# thumper2_v0001.net
KiCad netlist of a schematic drawn in EAGLE
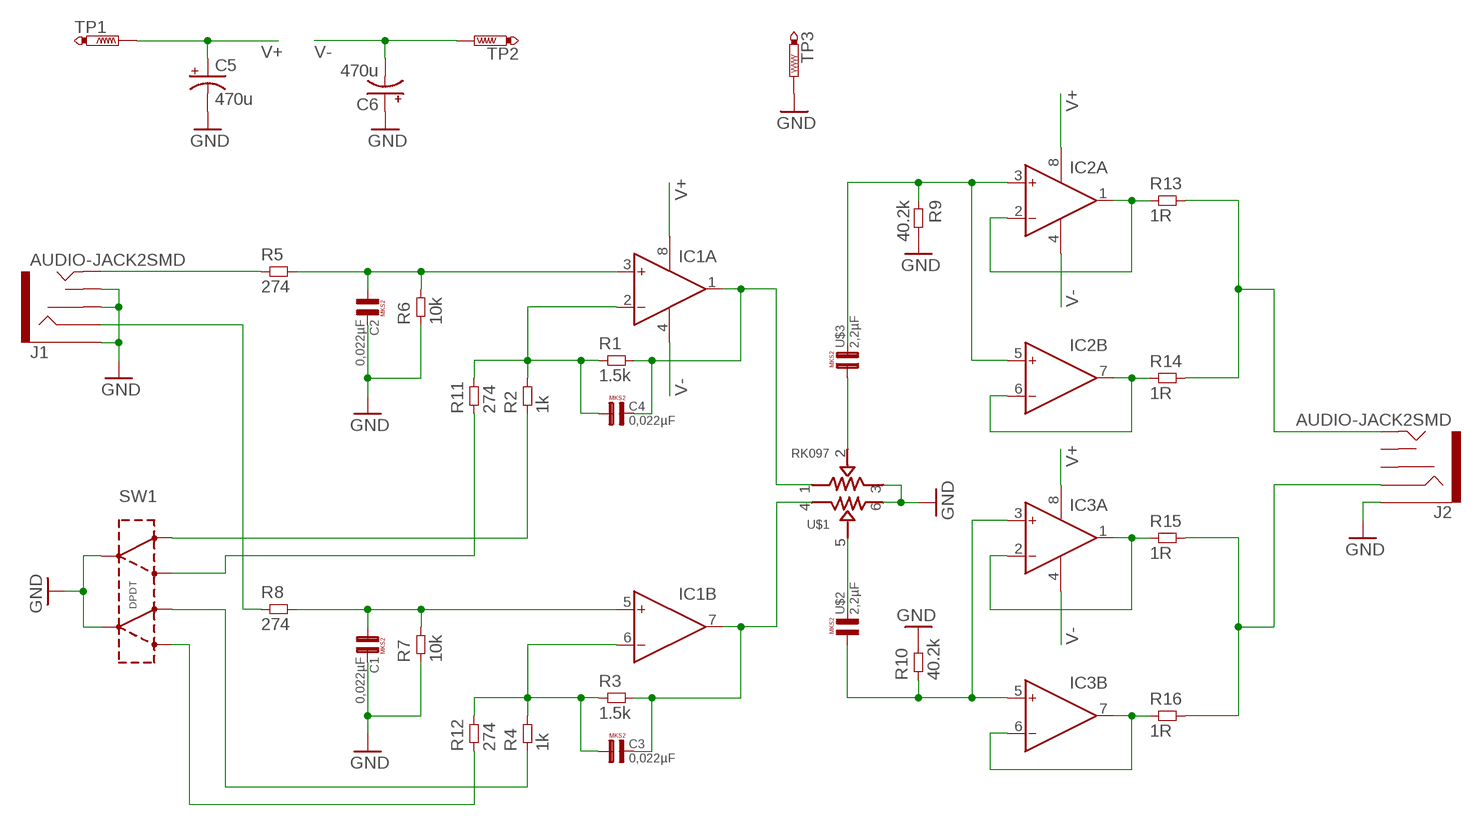
[diagram p0: schematic, sheet 1]

(export (version "E")
  (design (tool "Eeschema 10.0.6"))
  (components
    (comp (ref "C1")
      (value "0,022µF")
      (footprint "eagle-import:R5B2K5")
      (libsource (lib "eagle-import") (part "0,022µF"))
    )
    (comp (ref "C2")
      (value "0,022µF")
      (footprint "eagle-import:R5B2K5")
      (libsource (lib "eagle-import") (part "0,022µF"))
    )
    (comp (ref "C3")
      (value "0,022µF")
      (footprint "eagle-import:R5B2K5")
      (libsource (lib "eagle-import") (part "0,022µF"))
    )
    (comp (ref "C4")
      (value "0,022µF")
      (footprint "eagle-import:R5B2K5")
      (libsource (lib "eagle-import") (part "0,022µF"))
    )
    (comp (ref "C5")
      (value "470u")
      (footprint "eagle-import:153CLV-1010")
      (libsource (lib "eagle-import") (part "CPOL-US153CLV-1010"))
    )
    (comp (ref "C6")
      (value "470u")
      (footprint "eagle-import:153CLV-1010")
      (libsource (lib "eagle-import") (part "CPOL-US153CLV-1010"))
    )
    (comp (ref "IC1")
      (value "AD8620R")
      (footprint "eagle-import:SO8")
      (fields (field (name "MF") "ALTERA CORPORATION") (field (name "MPN") "AD8620ARZ"))
      (libsource (lib "eagle-import") (part "AD8620R"))
    )
    (comp (ref "IC2")
      (value "AD8620R")
      (footprint "eagle-import:SO8")
      (fields (field (name "MF") "ALTERA CORPORATION") (field (name "MPN") "AD8620ARZ"))
      (libsource (lib "eagle-import") (part "AD8620R"))
    )
    (comp (ref "IC3")
      (value "AD8620R")
      (footprint "eagle-import:SO8")
      (fields (field (name "MF") "ALTERA CORPORATION") (field (name "MPN") "AD8620ARZ"))
      (libsource (lib "eagle-import") (part "AD8620R"))
    )
    (comp (ref "J1")
      (value "AUDIO-JACK2SMD")
      (footprint "eagle-import:AUDIO-JACK-3.5MM-SMD")
      (libsource (lib "eagle-import") (part "AUDIO-JACK2SMD"))
    )
    (comp (ref "J2")
      (value "AUDIO-JACK2SMD")
      (footprint "eagle-import:AUDIO-JACK-3.5MM-SMD")
      (libsource (lib "eagle-import") (part "AUDIO-JACK2SMD"))
    )
    (comp (ref "R1")
      (value "1.5k")
      (footprint "eagle-import:0603L3")
      (libsource (lib "eagle-import") (part "RES0603L3"))
    )
    (comp (ref "R2")
      (value "1k")
      (footprint "eagle-import:0603L3")
      (libsource (lib "eagle-import") (part "RES0603L3"))
    )
    (comp (ref "R3")
      (value "1.5k")
      (footprint "eagle-import:0603L3")
      (libsource (lib "eagle-import") (part "RES0603L3"))
    )
    (comp (ref "R4")
      (value "1k")
      (footprint "eagle-import:0603L3")
      (libsource (lib "eagle-import") (part "RES0603L3"))
    )
    (comp (ref "R5")
      (value "274")
      (footprint "eagle-import:0603L3")
      (libsource (lib "eagle-import") (part "RES0603L3"))
    )
    (comp (ref "R6")
      (value "10k")
      (footprint "eagle-import:0603L3")
      (libsource (lib "eagle-import") (part "RES0603L3"))
    )
    (comp (ref "R7")
      (value "10k")
      (footprint "eagle-import:0603L3")
      (libsource (lib "eagle-import") (part "RES0603L3"))
    )
    (comp (ref "R8")
      (value "274")
      (footprint "eagle-import:0603L3")
      (libsource (lib "eagle-import") (part "RES0603L3"))
    )
    (comp (ref "R9")
      (value "40.2k")
      (footprint "eagle-import:0603L3")
      (libsource (lib "eagle-import") (part "RES0603L3"))
    )
    (comp (ref "R10")
      (value "40.2k")
      (footprint "eagle-import:0603L3")
      (libsource (lib "eagle-import") (part "RES0603L3"))
    )
    (comp (ref "R11")
      (value "274")
      (footprint "eagle-import:0603L3")
      (libsource (lib "eagle-import") (part "RES0603L3"))
    )
    (comp (ref "R12")
      (value "274")
      (footprint "eagle-import:0603L3")
      (libsource (lib "eagle-import") (part "RES0603L3"))
    )
    (comp (ref "R13")
      (value "1R")
      (footprint "eagle-import:1206L3")
      (libsource (lib "eagle-import") (part "RES1206L3"))
    )
    (comp (ref "R14")
      (value "1R")
      (footprint "eagle-import:1206L3")
      (libsource (lib "eagle-import") (part "RES1206L3"))
    )
    (comp (ref "R15")
      (value "1R")
      (footprint "eagle-import:1206L3")
      (libsource (lib "eagle-import") (part "RES1206L3"))
    )
    (comp (ref "R16")
      (value "1R")
      (footprint "eagle-import:1206L3")
      (libsource (lib "eagle-import") (part "RES1206L3"))
    )
    (comp (ref "SW1")
      (value "DPDTDPDT-2X2.5")
      (footprint "eagle-import:DPDT-2X2.5")
      (libsource (lib "eagle-import") (part "DPDTDPDT-2X2.5"))
    )
    (comp (ref "TP1")
      (value "PTR1PAD1-20")
      (footprint "eagle-import:P1-20")
      (libsource (lib "eagle-import") (part "PTR1PAD1-20"))
    )
    (comp (ref "TP2")
      (value "PTR1PAD1-20")
      (footprint "eagle-import:P1-20")
      (libsource (lib "eagle-import") (part "PTR1PAD1-20"))
    )
    (comp (ref "TP3")
      (value "PTR1PAD1-20")
      (footprint "eagle-import:P1-20")
      (libsource (lib "eagle-import") (part "PTR1PAD1-20"))
    )
    (comp (ref "U$1")
      (value "RK097")
      (footprint "eagle-import:RK097")
      (libsource (lib "eagle-import") (part "RK097"))
    )
    (comp (ref "U$2")
      (value "2,2µF")
      (footprint "eagle-import:R5B7K2")
      (libsource (lib "eagle-import") (part "2,2µF"))
    )
    (comp (ref "U$3")
      (value "2,2µF")
      (footprint "eagle-import:R5B7K2")
      (libsource (lib "eagle-import") (part "2,2µF"))
    )
  )
  (nets
    (net (code "1") (name "/V+") (class "Default")
      (node (ref "C5") (pin "+") (pinfunction "+_+") (pintype "passive"))
      (node (ref "IC1") (pin "8") (pinfunction "V+_8") (pintype "power_in"))
      (node (ref "IC2") (pin "8") (pinfunction "V+_8") (pintype "power_in"))
      (node (ref "IC3") (pin "8") (pinfunction "V+_8") (pintype "power_in"))
      (node (ref "TP1") (pin "TP") (pinfunction "TP_TP") (pintype "input"))
    )
    (net (code "2") (name "/V-") (class "Default")
      (node (ref "C6") (pin "-") (pinfunction "-_-") (pintype "passive"))
      (node (ref "IC1") (pin "4") (pinfunction "V-_4") (pintype "power_in"))
      (node (ref "IC2") (pin "4") (pinfunction "V-_4") (pintype "power_in"))
      (node (ref "IC3") (pin "4") (pinfunction "V-_4") (pintype "power_in"))
      (node (ref "TP2") (pin "TP") (pinfunction "TP_TP") (pintype "input"))
    )
    (net (code "3") (name "GND") (class "Default")
      (node (ref "C1") (pin "2") (pinfunction "2_2") (pintype "passive"))
      (node (ref "C2") (pin "2") (pinfunction "2_2") (pintype "passive"))
      (node (ref "C5") (pin "-") (pinfunction "-_-") (pintype "passive"))
      (node (ref "C6") (pin "+") (pinfunction "+_+") (pintype "passive"))
      (node (ref "J1") (pin "RSH") (pinfunction "RSH_RSH") (pintype "bidirectional"))
      (node (ref "J1") (pin "SLEEVE") (pinfunction "SLEEVE_SLEEVE") (pintype "bidirectional"))
      (node (ref "J1") (pin "TSH") (pinfunction "TSH_TSH") (pintype "bidirectional"))
      (node (ref "J2") (pin "SLEEVE") (pinfunction "SLEEVE_SLEEVE") (pintype "bidirectional"))
      (node (ref "R10") (pin "P$2") (pinfunction "2_P$2") (pintype "bidirectional"))
      (node (ref "R6") (pin "P$1") (pinfunction "1_P$1") (pintype "bidirectional"))
      (node (ref "R7") (pin "P$1") (pinfunction "1_P$1") (pintype "bidirectional"))
      (node (ref "R9") (pin "P$2") (pinfunction "2_P$2") (pintype "bidirectional"))
      (node (ref "SW1") (pin "2") (pinfunction "INA_2") (pintype "bidirectional"))
      (node (ref "SW1") (pin "5") (pinfunction "INB_5") (pintype "bidirectional"))
      (node (ref "TP3") (pin "TP") (pinfunction "TP_TP") (pintype "input"))
      (node (ref "U$1") (pin "3") (pinfunction "3_3") (pintype "bidirectional"))
      (node (ref "U$1") (pin "6") (pinfunction "6_6") (pintype "bidirectional"))
    )
    (net (code "4") (name "Net-(IC1A-IN+)") (class "Default")
      (node (ref "C2") (pin "1") (pinfunction "1_1") (pintype "passive"))
      (node (ref "IC1") (pin "3") (pinfunction "IN+_3") (pintype "input"))
      (node (ref "R5") (pin "P$2") (pinfunction "2_P$2") (pintype "bidirectional"))
      (node (ref "R6") (pin "P$2") (pinfunction "2_P$2") (pintype "bidirectional"))
    )
    (net (code "5") (name "Net-(IC1A-IN-)") (class "Default")
      (node (ref "C4") (pin "1") (pinfunction "1_1") (pintype "passive"))
      (node (ref "IC1") (pin "2") (pinfunction "IN-_2") (pintype "input"))
      (node (ref "R1") (pin "P$1") (pinfunction "1_P$1") (pintype "bidirectional"))
      (node (ref "R11") (pin "P$2") (pinfunction "2_P$2") (pintype "bidirectional"))
      (node (ref "R2") (pin "P$2") (pinfunction "2_P$2") (pintype "bidirectional"))
    )
    (net (code "6") (name "Net-(IC1A-OUT)") (class "Default")
      (node (ref "C4") (pin "2") (pinfunction "2_2") (pintype "passive"))
      (node (ref "IC1") (pin "1") (pinfunction "OUT_1") (pintype "output"))
      (node (ref "R1") (pin "P$2") (pinfunction "2_P$2") (pintype "bidirectional"))
      (node (ref "U$1") (pin "1") (pinfunction "1_1") (pintype "bidirectional"))
    )
    (net (code "7") (name "Net-(IC1B-IN+)") (class "Default")
      (node (ref "C1") (pin "1") (pinfunction "1_1") (pintype "passive"))
      (node (ref "IC1") (pin "5") (pinfunction "IN+_5") (pintype "input"))
      (node (ref "R7") (pin "P$2") (pinfunction "2_P$2") (pintype "bidirectional"))
      (node (ref "R8") (pin "P$2") (pinfunction "2_P$2") (pintype "bidirectional"))
    )
    (net (code "8") (name "Net-(IC1B-IN-)") (class "Default")
      (node (ref "C3") (pin "1") (pinfunction "1_1") (pintype "passive"))
      (node (ref "IC1") (pin "6") (pinfunction "IN-_6") (pintype "input"))
      (node (ref "R12") (pin "P$2") (pinfunction "2_P$2") (pintype "bidirectional"))
      (node (ref "R3") (pin "P$1") (pinfunction "1_P$1") (pintype "bidirectional"))
      (node (ref "R4") (pin "P$2") (pinfunction "2_P$2") (pintype "bidirectional"))
    )
    (net (code "9") (name "Net-(IC1B-OUT)") (class "Default")
      (node (ref "C3") (pin "2") (pinfunction "2_2") (pintype "passive"))
      (node (ref "IC1") (pin "7") (pinfunction "OUT_7") (pintype "output"))
      (node (ref "R3") (pin "P$2") (pinfunction "2_P$2") (pintype "bidirectional"))
      (node (ref "U$1") (pin "4") (pinfunction "4_4") (pintype "bidirectional"))
    )
    (net (code "10") (name "Net-(IC2A-IN+)") (class "Default")
      (node (ref "IC2") (pin "3") (pinfunction "IN+_3") (pintype "input"))
      (node (ref "IC2") (pin "5") (pinfunction "IN+_5") (pintype "input"))
      (node (ref "R9") (pin "P$1") (pinfunction "1_P$1") (pintype "bidirectional"))
      (node (ref "U$3") (pin "2") (pinfunction "2_2") (pintype "passive"))
    )
    (net (code "11") (name "Net-(IC2A-IN-)") (class "Default")
      (node (ref "IC2") (pin "1") (pinfunction "OUT_1") (pintype "output"))
      (node (ref "IC2") (pin "2") (pinfunction "IN-_2") (pintype "input"))
      (node (ref "R13") (pin "1") (pinfunction "1_1") (pintype "bidirectional"))
    )
    (net (code "12") (name "Net-(IC2B-IN-)") (class "Default")
      (node (ref "IC2") (pin "6") (pinfunction "IN-_6") (pintype "input"))
      (node (ref "IC2") (pin "7") (pinfunction "OUT_7") (pintype "output"))
      (node (ref "R14") (pin "1") (pinfunction "1_1") (pintype "bidirectional"))
    )
    (net (code "13") (name "Net-(IC3A-IN+)") (class "Default")
      (node (ref "IC3") (pin "3") (pinfunction "IN+_3") (pintype "input"))
      (node (ref "IC3") (pin "5") (pinfunction "IN+_5") (pintype "input"))
      (node (ref "R10") (pin "P$1") (pinfunction "1_P$1") (pintype "bidirectional"))
      (node (ref "U$2") (pin "1") (pinfunction "1_1") (pintype "passive"))
    )
    (net (code "14") (name "Net-(IC3A-IN-)") (class "Default")
      (node (ref "IC3") (pin "1") (pinfunction "OUT_1") (pintype "output"))
      (node (ref "IC3") (pin "2") (pinfunction "IN-_2") (pintype "input"))
      (node (ref "R15") (pin "1") (pinfunction "1_1") (pintype "bidirectional"))
    )
    (net (code "15") (name "Net-(IC3B-IN-)") (class "Default")
      (node (ref "IC3") (pin "6") (pinfunction "IN-_6") (pintype "input"))
      (node (ref "IC3") (pin "7") (pinfunction "OUT_7") (pintype "output"))
      (node (ref "R16") (pin "1") (pinfunction "1_1") (pintype "bidirectional"))
    )
    (net (code "16") (name "Net-(J2-PadRING)") (class "Default")
      (node (ref "J2") (pin "RING") (pinfunction "RING_RING") (pintype "bidirectional"))
      (node (ref "R15") (pin "2") (pinfunction "2_2") (pintype "bidirectional"))
      (node (ref "R16") (pin "2") (pinfunction "2_2") (pintype "bidirectional"))
    )
    (net (code "17") (name "Net-(J2-PadTIP)") (class "Default")
      (node (ref "J2") (pin "TIP") (pinfunction "TIP_TIP") (pintype "bidirectional"))
      (node (ref "R13") (pin "2") (pinfunction "2_2") (pintype "bidirectional"))
      (node (ref "R14") (pin "2") (pinfunction "2_2") (pintype "bidirectional"))
    )
    (net (code "18") (name "Net-(R2-1)") (class "Default")
      (node (ref "R2") (pin "P$1") (pinfunction "1_P$1") (pintype "bidirectional"))
      (node (ref "SW1") (pin "1") (pinfunction "OUTA1_1") (pintype "bidirectional"))
    )
    (net (code "19") (name "Net-(R4-1)") (class "Default")
      (node (ref "R4") (pin "P$1") (pinfunction "1_P$1") (pintype "bidirectional"))
      (node (ref "SW1") (pin "4") (pinfunction "OUTB1_4") (pintype "bidirectional"))
    )
    (net (code "20") (name "Net-(R5-1)") (class "Default")
      (node (ref "J1") (pin "TIP") (pinfunction "TIP_TIP") (pintype "bidirectional"))
      (node (ref "R5") (pin "P$1") (pinfunction "1_P$1") (pintype "bidirectional"))
    )
    (net (code "21") (name "Net-(R8-1)") (class "Default")
      (node (ref "J1") (pin "RING") (pinfunction "RING_RING") (pintype "bidirectional"))
      (node (ref "R8") (pin "P$1") (pinfunction "1_P$1") (pintype "bidirectional"))
    )
    (net (code "22") (name "Net-(R11-1)") (class "Default")
      (node (ref "R11") (pin "P$1") (pinfunction "1_P$1") (pintype "bidirectional"))
      (node (ref "SW1") (pin "3") (pinfunction "OUTA2_3") (pintype "bidirectional"))
    )
    (net (code "23") (name "Net-(R12-1)") (class "Default")
      (node (ref "R12") (pin "P$1") (pinfunction "1_P$1") (pintype "bidirectional"))
      (node (ref "SW1") (pin "6") (pinfunction "OUTB2_6") (pintype "bidirectional"))
    )
    (net (code "24") (name "Net-(U$1-Pad2)") (class "Default")
      (node (ref "U$1") (pin "2") (pinfunction "2_2") (pintype "bidirectional"))
      (node (ref "U$3") (pin "1") (pinfunction "1_1") (pintype "passive"))
    )
    (net (code "25") (name "Net-(U$1-Pad5)") (class "Default")
      (node (ref "U$1") (pin "5") (pinfunction "5_5") (pintype "bidirectional"))
      (node (ref "U$2") (pin "2") (pinfunction "2_2") (pintype "passive"))
    )
    (net (code "26") (name "unconnected-(J2-PadRSH)") (class "Default")
      (node (ref "J2") (pin "RSH") (pinfunction "RSH_RSH") (pintype "bidirectional"))
    )
    (net (code "27") (name "unconnected-(J2-PadTSH)") (class "Default")
      (node (ref "J2") (pin "TSH") (pinfunction "TSH_TSH") (pintype "bidirectional"))
    )
  )
)
